# OSO-MISC-20-006_Analog_Combo.net
KiCad netlist of a schematic drawn in EAGLE
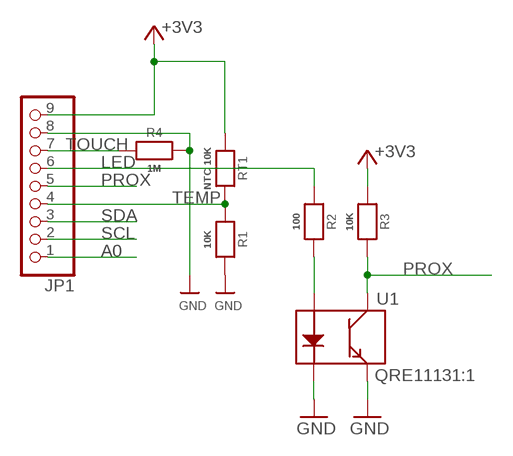
[diagram p0: schematic, sheet 1]

(export (version "E")
  (design (tool "Eeschema 10.0.6"))
  (components
    (comp (ref "JP1")
      (value "HEADER-1X9_JSTSH")
      (footprint "eagle-import:JST_SH9")
      (libsource (lib "eagle-import") (part "HEADER-1X9_JSTSH"))
    )
    (comp (ref "R1")
      (value "10K")
      (footprint "eagle-import:0805-NO")
      (libsource (lib "eagle-import") (part "RESISTOR0805_NOOUTLINE"))
    )
    (comp (ref "R2")
      (value "100")
      (footprint "eagle-import:0805-NO")
      (libsource (lib "eagle-import") (part "RESISTOR0805_NOOUTLINE"))
    )
    (comp (ref "R3")
      (value "10K")
      (footprint "eagle-import:0805-NO")
      (libsource (lib "eagle-import") (part "RESISTOR0805_NOOUTLINE"))
    )
    (comp (ref "R4")
      (value "1M")
      (footprint "eagle-import:0805-NO")
      (libsource (lib "eagle-import") (part "RESISTOR0805_NOOUTLINE"))
    )
    (comp (ref "RT1")
      (value "NTC 10K")
      (footprint "eagle-import:0805-NO")
      (libsource (lib "eagle-import") (part "RESISTOR0805_NOOUTLINE"))
    )
    (comp (ref "U1")
      (value "QRE11131:1")
      (footprint "eagle-import:QRE1113-1_1")
      (libsource (lib "eagle-import") (part "QRE11131{colon}1"))
    )
  )
  (nets
    (net (code "1") (name "+3V3") (class "Default")
      (node (ref "JP1") (pin "9") (pinfunction "9_9") (pintype "passive"))
      (node (ref "R3") (pin "1") (pinfunction "1_1") (pintype "passive"))
      (node (ref "RT1") (pin "1") (pinfunction "1_1") (pintype "passive"))
    )
    (net (code "2") (name "/A0") (class "Default")
      (node (ref "JP1") (pin "1") (pinfunction "1_1") (pintype "passive"))
    )
    (net (code "3") (name "/LED") (class "Default")
      (node (ref "JP1") (pin "6") (pinfunction "6_6") (pintype "passive"))
      (node (ref "R2") (pin "1") (pinfunction "1_1") (pintype "passive"))
    )
    (net (code "4") (name "/PROX") (class "Default")
      (node (ref "JP1") (pin "5") (pinfunction "5_5") (pintype "passive"))
      (node (ref "R3") (pin "2") (pinfunction "2_2") (pintype "passive"))
      (node (ref "U1") (pin "3") (pinfunction "C_3") (pintype "bidirectional"))
    )
    (net (code "5") (name "/SCL") (class "Default")
      (node (ref "JP1") (pin "2") (pinfunction "2_2") (pintype "passive"))
    )
    (net (code "6") (name "/SDA") (class "Default")
      (node (ref "JP1") (pin "3") (pinfunction "3_3") (pintype "passive"))
    )
    (net (code "7") (name "/TEMP") (class "Default")
      (node (ref "JP1") (pin "4") (pinfunction "4_4") (pintype "passive"))
      (node (ref "R1") (pin "1") (pinfunction "1_1") (pintype "passive"))
      (node (ref "RT1") (pin "2") (pinfunction "2_2") (pintype "passive"))
    )
    (net (code "8") (name "/TOUCH") (class "Default")
      (node (ref "JP1") (pin "7") (pinfunction "7_7") (pintype "passive"))
      (node (ref "R4") (pin "1") (pinfunction "1_1") (pintype "passive"))
    )
    (net (code "9") (name "GND") (class "Default")
      (node (ref "JP1") (pin "8") (pinfunction "8_8") (pintype "passive"))
      (node (ref "R1") (pin "2") (pinfunction "2_2") (pintype "passive"))
      (node (ref "R4") (pin "2") (pinfunction "2_2") (pintype "passive"))
      (node (ref "U1") (pin "2") (pinfunction "K_2") (pintype "bidirectional"))
      (node (ref "U1") (pin "4") (pinfunction "E_4") (pintype "bidirectional"))
    )
    (net (code "10") (name "Net-(U1-A)") (class "Default")
      (node (ref "R2") (pin "2") (pinfunction "2_2") (pintype "passive"))
      (node (ref "U1") (pin "1") (pinfunction "A_1") (pintype "bidirectional"))
    )
  )
)
